# JTAG_Flash_Update.net
KiCad netlist of a schematic drawn in Altium Designer
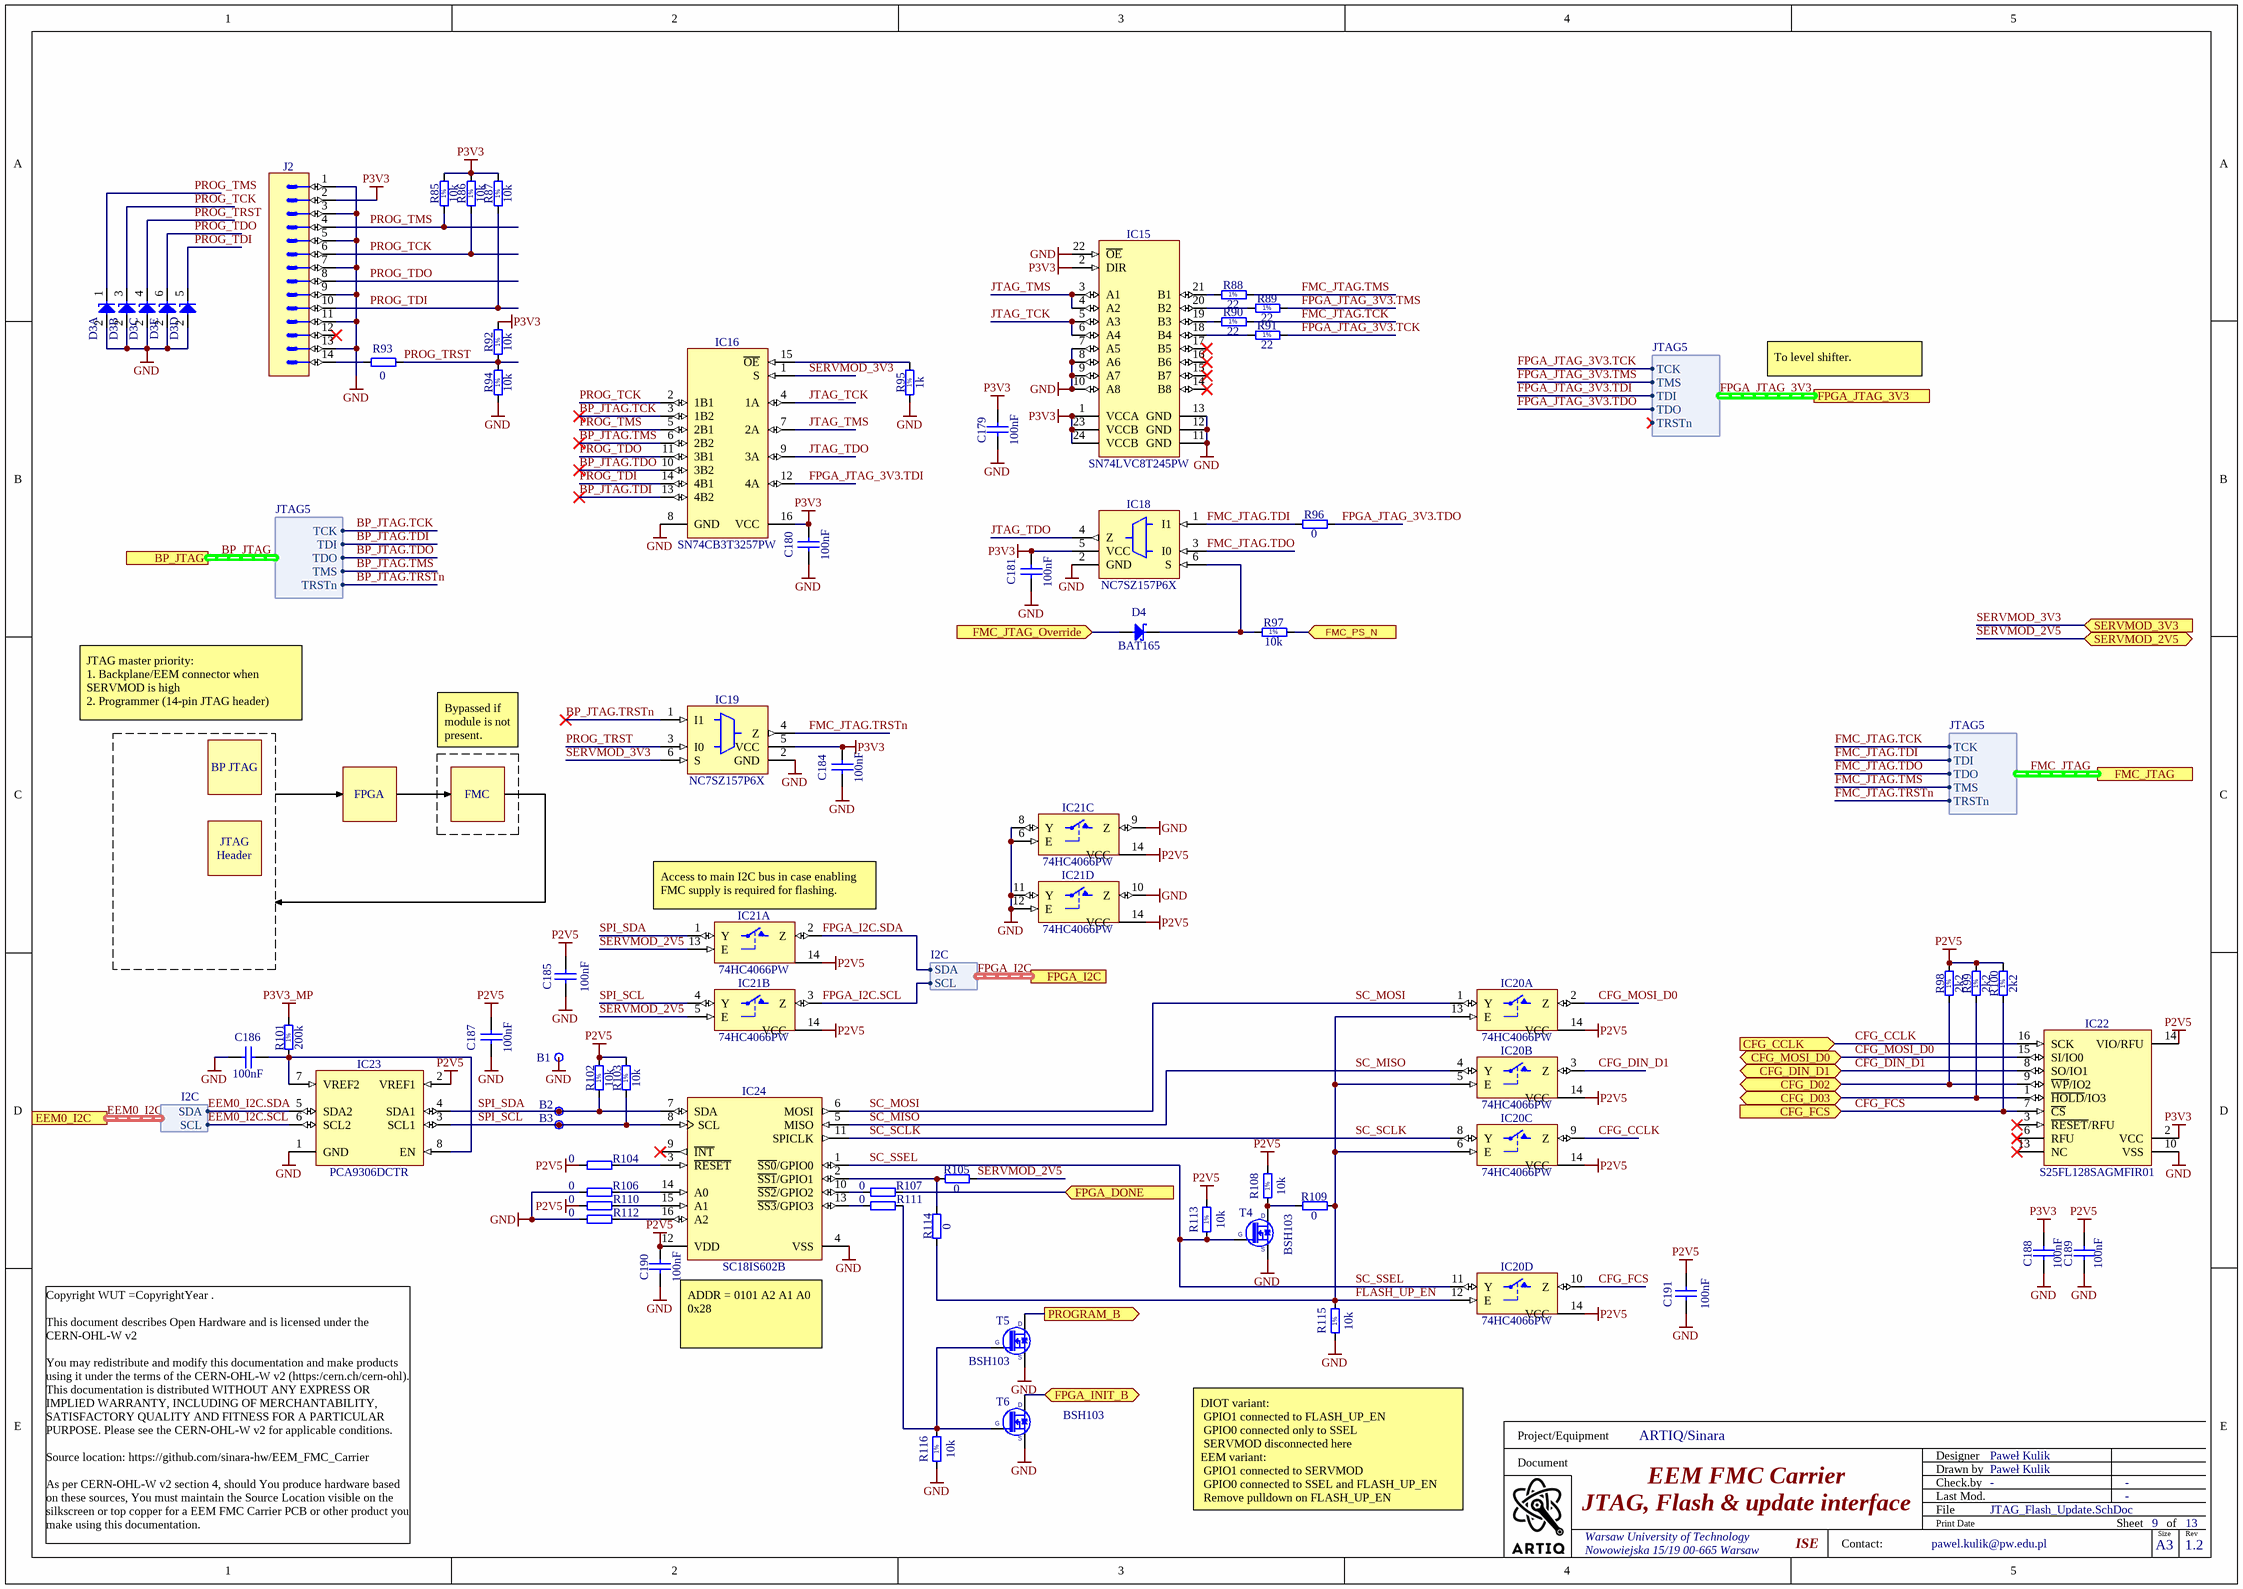
[diagram p0: JTAG_Flash_Update.SchDoc]

(export (version "E")
  (design (tool "Eeschema 10.0.6"))
  (components
    (comp (ref "B1")
      (value "Plated Hole")
      (footprint "c150h100")
      (description "Single Terminal Socket")
      (fields (field (name "PART NUMBER") "PLATED_HOLE1.0_PAD1.5") (field (name "AUTHOR") "CERN DEM JLC"))
      (libsource (lib "Eletro-mechanical") (part "Single Terminal Socket"))
    )
    (comp (ref "B2")
      (value "Test Point")
      (footprint "TPS127")
      (fields (field (name "PART NUMBER") "SMD_PAD_1.27X1.27MM") (field (name "AUTHOR") "CERN DEM JLC"))
      (libsource (lib "Eletro-mechanical") (part "Test Point"))
    )
    (comp (ref "B3")
      (value "Test Point")
      (footprint "TPS127")
      (fields (field (name "PART NUMBER") "SMD_PAD_1.27X1.27MM") (field (name "AUTHOR") "CERN DEM JLC"))
      (libsource (lib "Eletro-mechanical") (part "Test Point"))
    )
    (comp (ref "C179")
      (value "100nF")
      (footprint "CAPC1005X55N")
      (description "Non-polarised capacitor")
      (fields
        (field (name "PART NUMBER") "CC0402_100NF_25V_10%_X7R_YUDEN_TMK105B7104KVHF")
        (field (name "VOLTAGE") "25V")
        (field (name "AUTHOR") "CERN DEM JLC")
      )
      (libsource (lib "Capacitors") (part "Capacitor - non polarized"))
    )
    (comp (ref "C180")
      (value "100nF")
      (footprint "CAPC1005X55N")
      (description "Non-polarised capacitor")
      (fields
        (field (name "PART NUMBER") "CC0402_100NF_25V_10%_X7R_YUDEN_TMK105B7104KVHF")
        (field (name "VOLTAGE") "25V")
        (field (name "AUTHOR") "CERN DEM JLC")
      )
      (libsource (lib "Capacitors") (part "Capacitor - non polarized"))
    )
    (comp (ref "C181")
      (value "100nF")
      (footprint "CAPC1005X55N")
      (description "Non-polarised capacitor")
      (fields
        (field (name "PART NUMBER") "CC0402_100NF_25V_10%_X7R_YUDEN_TMK105B7104KVHF")
        (field (name "VOLTAGE") "25V")
        (field (name "AUTHOR") "CERN DEM JLC")
      )
      (libsource (lib "Capacitors") (part "Capacitor - non polarized"))
    )
    (comp (ref "C184")
      (value "100nF")
      (footprint "CAPC1005X55N")
      (description "Non-polarised capacitor")
      (fields
        (field (name "PART NUMBER") "CC0402_100NF_25V_10%_X7R_YUDEN_TMK105B7104KVHF")
        (field (name "VOLTAGE") "25V")
        (field (name "AUTHOR") "CERN DEM JLC")
      )
      (libsource (lib "Capacitors") (part "Capacitor - non polarized"))
    )
    (comp (ref "C185")
      (value "100nF")
      (footprint "CAPC1005X55N")
      (description "Non-polarised capacitor")
      (fields
        (field (name "PART NUMBER") "CC0402_100NF_16V_10%_X5R")
        (field (name "VOLTAGE") "16V")
        (field (name "AUTHOR") "CERN DEM JLC")
      )
      (libsource (lib "Capacitors") (part "Capacitor - non polarized"))
    )
    (comp (ref "C186")
      (value "100nF")
      (footprint "CAPC1005X55N")
      (description "Non-polarised capacitor")
      (fields
        (field (name "PART NUMBER") "CC0402_100NF_25V_10%_X7R_YUDEN_TMK105B7104KVHF")
        (field (name "VOLTAGE") "25V")
        (field (name "AUTHOR") "CERN DEM JLC")
      )
      (libsource (lib "Capacitors") (part "Capacitor - non polarized"))
    )
    (comp (ref "C187")
      (value "100nF")
      (footprint "CAPC1005X55N")
      (description "Non-polarised capacitor")
      (fields
        (field (name "PART NUMBER") "CC0402_100NF_25V_10%_X7R_YUDEN_TMK105B7104KVHF")
        (field (name "VOLTAGE") "25V")
        (field (name "AUTHOR") "CERN DEM JLC")
      )
      (libsource (lib "Capacitors") (part "Capacitor - non polarized"))
    )
    (comp (ref "C188")
      (value "100nF")
      (footprint "CAPC0603X33N")
      (description "Non-polarised capacitor")
      (fields
        (field (name "PART NUMBER") "CC0201_100NF_6.3V_10%_X5R")
        (field (name "VOLTAGE") "6.3V")
        (field (name "AUTHOR") "CERN DEM JLC")
      )
      (libsource (lib "Capacitors") (part "Capacitor - non polarized"))
    )
    (comp (ref "C189")
      (value "100nF")
      (footprint "CAPC0603X33N")
      (description "Non-polarised capacitor")
      (fields
        (field (name "PART NUMBER") "CC0201_100NF_6.3V_10%_X5R")
        (field (name "VOLTAGE") "6.3V")
        (field (name "AUTHOR") "CERN DEM JLC")
      )
      (libsource (lib "Capacitors") (part "Capacitor - non polarized"))
    )
    (comp (ref "C190")
      (value "100nF")
      (footprint "CAPC1005X55N")
      (description "Non-polarised capacitor")
      (fields
        (field (name "PART NUMBER") "CC0402_100NF_16V_10%_X5R")
        (field (name "VOLTAGE") "16V")
        (field (name "AUTHOR") "CERN DEM JLC")
      )
      (libsource (lib "Capacitors") (part "Capacitor - non polarized"))
    )
    (comp (ref "C191")
      (value "100nF")
      (footprint "CAPC1005X55N")
      (description "Non-polarised capacitor")
      (fields
        (field (name "PART NUMBER") "CC0402_100NF_16V_10%_X5R")
        (field (name "VOLTAGE") "16V")
        (field (name "AUTHOR") "CERN DEM JLC")
      )
      (libsource (lib "Capacitors") (part "Capacitor - non polarized"))
    )
    (comp (ref "D3")
      (value "PESD3V3L5UY")
      (footprint "SOT65P210X110-6N")
      (description "Fivefold ESD Protection Diode Arrays")
      (fields
        (field (name "VOLTAGE") "3.3V")
        (field (name "POWER") "200W")
        (field (name "AUTHOR") "CERN DEM WB")
      )
      (libsource (lib "ICs And Semiconductors") (part "PESD Array 5diodes 6pins Common anode2"))
    )
    (comp (ref "D4")
      (value "BAT165")
      (footprint "SOD2512X110N")
      (description "Schottky Diode")
      (fields
        (field (name "MANUFACTURER") "INFINEON")
        (field (name "VOLTAGE") "40V")
        (field (name "AUTHOR") "CERN DEM JLC")
      )
      (libsource (lib "ICs And Semiconductors") (part "Diode Schottky"))
    )
    (comp (ref "IC15")
      (value "SN74LVC8T245PW")
      (footprint "SOP65P640X120-24N")
      (description "8-Bit Dual-Supply Bus Transceiver With Configurable Voltage Translation and 3-State Outputs")
      (fields (field (name "MANUFACTURER") "TEXAS INSTRUMENTS") (field (name "AUTHOR") "CERN DEM JLC"))
      (libsource (lib "ICs And Semiconductors") (part "748T245"))
    )
    (comp (ref "IC16")
      (value "SN74CB3T3257PW")
      (footprint "SOP65P640X120-16N")
      (description "4-BIT 1-OF-2 FET Multiplexer/Demultiplexer 2.5V/3.3V Low-Voltage Bus Switch 5V Tolerant Shifter")
      (fields (field (name "MANUFACTURER") "TEXAS INSTRUMENTS") (field (name "AUTHOR") "CERN DEM JLC"))
      (libsource (lib "ICs And Semiconductors") (part "743257"))
    )
    (comp (ref "IC18")
      (value "NC7SZ157P6X")
      (footprint "SOT65P210X110-6N")
      (description "TinyLogic® UHS 2-Input Non-Inverting Multiplexer")
      (fields (field (name "MANUFACTURER") "FAIRCHILD SEMICONDUCTOR") (field (name "AUTHOR") "CERN DEM JLC"))
      (libsource (lib "") (part "NC7SZ157_1"))
    )
    (comp (ref "IC19")
      (value "NC7SZ157P6X")
      (footprint "SOT65P210X110-6N")
      (description "TinyLogic® UHS 2-Input Non-Inverting Multiplexer")
      (fields (field (name "MANUFACTURER") "FAIRCHILD SEMICONDUCTOR") (field (name "AUTHOR") "CERN DEM JLC"))
      (libsource (lib "ICs And Semiconductors") (part "NC7SZ157"))
    )
    (comp (ref "IC20")
      (value "74HC4066PW")
      (footprint "SOP65P640X110-14N")
      (fields (field (name "MANUFACTURER") "NXP SEMICONDUCTORS") (field (name "AUTHOR") "CERN DEM JLC"))
      (libsource (lib "ICs And Semiconductors") (part "4066"))
    )
    (comp (ref "IC21")
      (value "74HC4066PW")
      (footprint "SOP65P640X110-14N")
      (fields (field (name "MANUFACTURER") "NXP SEMICONDUCTORS") (field (name "AUTHOR") "CERN DEM JLC"))
      (libsource (lib "ICs And Semiconductors") (part "4066"))
    )
    (comp (ref "IC22")
      (value "S25FL128SAGMFIR01")
      (footprint "SOIC127P1030X265-16N")
      (fields (field (name "MANUFACTURER") "SPANSION") (field (name "AUTHOR") "CERN DEM JLC"))
      (libsource (lib "ICs And Semiconductors") (part "S25FL128SAGMFIR01"))
    )
    (comp (ref "IC23")
      (value "PCA9306DCTR")
      (footprint "SOP65P400X130-8N")
      (description "Dual Bidirectional I2C Bus And SMBus Voltage-Level Translator")
      (fields (field (name "MANUFACTURER") "TEXAS INSTRUMENTS") (field (name "AUTHOR") "CERN DEM JLC"))
      (libsource (lib "ICs And Semiconductors") (part "PCA9306D"))
    )
    (comp (ref "IC24")
      (value "SC18IS602B")
      (footprint "SOP65P640X110-16N")
      (description "I2C-bus to SPI bridge")
      (fields (field (name "MANUFACTURER") "NXP SEMICONDUCTORS") (field (name "AUTHOR") "CERN DEM MR"))
      (libsource (lib "ICs And Semiconductors") (part "SC18IS602B"))
    )
    (comp (ref "J2")
      (value "Milli-Grid™")
      (footprint "MOLEX_87832-1420")
      (description "Connector 14 Male")
      (fields
        (field (name "PART NUMBER") "MOLEX_87832-1420")
        (field (name "MANUFACTURER") "MOLEX")
        (field (name "AUTHOR") "CERN DEM JLC")
      )
      (libsource (lib "Connectors") (part "Connector 14 Male"))
    )
    (comp (ref "R85")
      (value "10k")
      (footprint "RESC1005X40N")
      (description "Resistor - 1%")
      (fields
        (field (name "PART NUMBER") "R0402_10K_1%_0.0625W_100PPM")
        (field (name "POWER") "0.0625W")
        (field (name "AUTHOR") "CERN DEM JLC")
      )
      (libsource (lib "Resistors") (part "Resistor - 1%"))
    )
    (comp (ref "R86")
      (value "10k")
      (footprint "RESC1005X40N")
      (description "Resistor - 1%")
      (fields
        (field (name "PART NUMBER") "R0402_10K_1%_0.0625W_100PPM")
        (field (name "POWER") "0.0625W")
        (field (name "AUTHOR") "CERN DEM JLC")
      )
      (libsource (lib "Resistors") (part "Resistor - 1%"))
    )
    (comp (ref "R87")
      (value "10k")
      (footprint "RESC1005X40N")
      (description "Resistor - 1%")
      (fields
        (field (name "PART NUMBER") "R0402_10K_1%_0.0625W_100PPM")
        (field (name "POWER") "0.0625W")
        (field (name "AUTHOR") "CERN DEM JLC")
      )
      (libsource (lib "Resistors") (part "Resistor - 1%"))
    )
    (comp (ref "R88")
      (value "22")
      (footprint "RESC1005X40N")
      (description "Resistor - 1%")
      (fields
        (field (name "PART NUMBER") "R0402_22R_1%_0.0625W_100PPM")
        (field (name "POWER") "0.0625W")
        (field (name "AUTHOR") "CERN DEM JLC")
      )
      (libsource (lib "Resistors") (part "Resistor - 1%"))
    )
    (comp (ref "R89")
      (value "22")
      (footprint "RESC1005X40N")
      (description "Resistor - 1%")
      (fields
        (field (name "PART NUMBER") "R0402_22R_1%_0.0625W_100PPM")
        (field (name "POWER") "0.0625W")
        (field (name "AUTHOR") "CERN DEM JLC")
      )
      (libsource (lib "Resistors") (part "Resistor - 1%"))
    )
    (comp (ref "R90")
      (value "22")
      (footprint "RESC1005X40N")
      (description "Resistor - 1%")
      (fields
        (field (name "PART NUMBER") "R0402_22R_1%_0.0625W_100PPM")
        (field (name "POWER") "0.0625W")
        (field (name "AUTHOR") "CERN DEM JLC")
      )
      (libsource (lib "Resistors") (part "Resistor - 1%"))
    )
    (comp (ref "R91")
      (value "22")
      (footprint "RESC1005X40N")
      (description "Resistor - 1%")
      (fields
        (field (name "PART NUMBER") "R0402_22R_1%_0.0625W_100PPM")
        (field (name "POWER") "0.0625W")
        (field (name "AUTHOR") "CERN DEM JLC")
      )
      (libsource (lib "Resistors") (part "Resistor - 1%"))
    )
    (comp (ref "R92")
      (value "10k")
      (footprint "RESC1005X40N")
      (description "Resistor - 1%")
      (fields
        (field (name "PART NUMBER") "R0402_10K_1%_0.0625W_100PPM")
        (field (name "POWER") "0.0625W")
        (field (name "AUTHOR") "CERN DEM JLC")
      )
      (libsource (lib "Resistors") (part "Resistor - 1%"))
    )
    (comp (ref "R93")
      (value "0")
      (footprint "RESC1005X40N")
      (description "Resistor")
      (fields
        (field (name "MANUFACTURER PART NUMBER") "R0402_0R_JUMPER")
        (field (name "MANUFACTURER") "GENERIC")
        (field (name "AUTHOR") "CERN DEM JLC")
      )
      (libsource (lib "Resistors") (part "Resistor"))
    )
    (comp (ref "R94")
      (value "10k")
      (footprint "RESC1005X40N")
      (description "Resistor - 1%")
      (fields
        (field (name "PART NUMBER") "R0402_10K_1%_0.0625W_100PPM")
        (field (name "POWER") "0.0625W")
        (field (name "AUTHOR") "CERN DEM JLC")
      )
      (libsource (lib "Resistors") (part "Resistor - 1%"))
    )
    (comp (ref "R95")
      (value "1k")
      (footprint "RESC1005X40N")
      (description "Resistor - 1%")
      (fields
        (field (name "PART NUMBER") "R0402_1K_1%_0.0625W_100PPM")
        (field (name "POWER") "0.0625W")
        (field (name "AUTHOR") "CERN DEM JLC")
      )
      (libsource (lib "Resistors") (part "Resistor - 1%"))
    )
    (comp (ref "R96")
      (value "0")
      (footprint "RESC1005X40N")
      (description "Resistor")
      (fields
        (field (name "MANUFACTURER PART NUMBER") "R0402_0R_JUMPER")
        (field (name "MANUFACTURER") "GENERIC")
        (field (name "AUTHOR") "CERN DEM JLC")
      )
      (libsource (lib "Resistors") (part "Resistor"))
    )
    (comp (ref "R97")
      (value "10k")
      (footprint "RESC1005X40N")
      (description "Resistor - 1%")
      (fields
        (field (name "MANUFACTURER PART NUMBER") "R0402_10K_1%_0.0625W_100PPM")
        (field (name "MANUFACTURER") "GENERIC")
        (field (name "AUTHOR") "CERN DEM JLC")
      )
      (libsource (lib "Resistors") (part "Resistor - 1%"))
    )
    (comp (ref "R98")
      (value "2k2")
      (footprint "RESC1005X40N")
      (description "Resistor - 1%")
      (fields
        (field (name "PART NUMBER") "R0402_2K2_1%_0.0625W_100PPM")
        (field (name "POWER") "0.0625W")
        (field (name "AUTHOR") "CERN DEM JLC")
      )
      (libsource (lib "Resistors") (part "Resistor - 1%"))
    )
    (comp (ref "R99")
      (value "2k2")
      (footprint "RESC1005X40N")
      (description "Resistor - 1%")
      (fields
        (field (name "PART NUMBER") "R0402_2K2_1%_0.0625W_100PPM")
        (field (name "POWER") "0.0625W")
        (field (name "AUTHOR") "CERN DEM JLC")
      )
      (libsource (lib "Resistors") (part "Resistor - 1%"))
    )
    (comp (ref "R100")
      (value "2k2")
      (footprint "RESC1005X40N")
      (description "Resistor - 1%")
      (fields
        (field (name "PART NUMBER") "R0402_2K2_1%_0.0625W_100PPM")
        (field (name "POWER") "0.0625W")
        (field (name "AUTHOR") "CERN DEM JLC")
      )
      (libsource (lib "Resistors") (part "Resistor - 1%"))
    )
    (comp (ref "R101")
      (value "200k")
      (footprint "RESC1005X40N")
      (description "Resistor - 1%")
      (fields
        (field (name "PART NUMBER") "R0402_200K_1%_0.0625W_100PPM")
        (field (name "POWER") "0.0625W")
        (field (name "AUTHOR") "CERN DEM JLC")
      )
      (libsource (lib "Resistors") (part "Resistor - 1%"))
    )
    (comp (ref "R102")
      (value "10k")
      (footprint "RESC1005X40N")
      (description "Resistor - 1%")
      (fields
        (field (name "PART NUMBER") "R0402_10K_1%_0.0625W_100PPM")
        (field (name "POWER") "0.0625W")
        (field (name "AUTHOR") "CERN DEM JLC")
      )
      (libsource (lib "Resistors") (part "Resistor - 1%"))
    )
    (comp (ref "R103")
      (value "10k")
      (footprint "RESC1005X40N")
      (description "Resistor - 1%")
      (fields
        (field (name "PART NUMBER") "R0402_10K_1%_0.0625W_100PPM")
        (field (name "POWER") "0.0625W")
        (field (name "AUTHOR") "CERN DEM JLC")
      )
      (libsource (lib "Resistors") (part "Resistor - 1%"))
    )
    (comp (ref "R104")
      (value "0")
      (footprint "RESC1005X40N")
      (description "Resistor")
      (fields
        (field (name "PART NUMBER") "R0402_0R_JUMPER")
        (field (name "MANUFACTURER") "GENERIC")
        (field (name "AUTHOR") "CERN DEM JLC")
      )
      (libsource (lib "Resistors") (part "Resistor"))
    )
    (comp (ref "R105")
      (value "0")
      (footprint "RESC1005X40N")
      (description "Resistor")
      (fields
        (field (name "PART NUMBER") "R0402_0R_JUMPER")
        (field (name "MANUFACTURER") "GENERIC")
        (field (name "AUTHOR") "CERN DEM JLC")
      )
      (libsource (lib "Resistors") (part "Resistor"))
    )
    (comp (ref "R106")
      (value "0")
      (footprint "RESC1005X40N")
      (description "Resistor")
      (fields
        (field (name "PART NUMBER") "R0402_0R_JUMPER")
        (field (name "MANUFACTURER") "GENERIC")
        (field (name "AUTHOR") "CERN DEM JLC")
      )
      (libsource (lib "Resistors") (part "Resistor"))
    )
    (comp (ref "R107")
      (value "0")
      (footprint "RESC1005X40N")
      (description "Resistor")
      (fields
        (field (name "PART NUMBER") "R0402_0R_JUMPER")
        (field (name "MANUFACTURER") "GENERIC")
        (field (name "AUTHOR") "CERN DEM JLC")
      )
      (libsource (lib "Resistors") (part "Resistor"))
    )
    (comp (ref "R108")
      (value "10k")
      (footprint "RESC1005X40N")
      (description "Resistor - 1%")
      (fields
        (field (name "PART NUMBER") "R0402_10K_1%_0.0625W_100PPM")
        (field (name "POWER") "0.0625W")
        (field (name "AUTHOR") "CERN DEM JLC")
      )
      (libsource (lib "Resistors") (part "Resistor - 1%"))
    )
    (comp (ref "R109")
      (value "0")
      (footprint "RESC1005X40N")
      (description "Resistor")
      (fields
        (field (name "PART NUMBER") "R0402_0R_JUMPER")
        (field (name "MANUFACTURER") "GENERIC")
        (field (name "AUTHOR") "CERN DEM JLC")
      )
      (libsource (lib "Resistors") (part "Resistor"))
    )
    (comp (ref "R110")
      (value "0")
      (footprint "RESC1005X40N")
      (description "Resistor")
      (fields
        (field (name "PART NUMBER") "R0402_0R_JUMPER")
        (field (name "MANUFACTURER") "GENERIC")
        (field (name "AUTHOR") "CERN DEM JLC")
      )
      (libsource (lib "Resistors") (part "Resistor"))
    )
    (comp (ref "R111")
      (value "0")
      (footprint "RESC1005X40N")
      (description "Resistor")
      (fields
        (field (name "PART NUMBER") "R0402_0R_JUMPER")
        (field (name "MANUFACTURER") "GENERIC")
        (field (name "AUTHOR") "CERN DEM JLC")
      )
      (libsource (lib "Resistors") (part "Resistor"))
    )
    (comp (ref "R112")
      (value "0")
      (footprint "RESC1005X40N")
      (description "Resistor")
      (fields
        (field (name "PART NUMBER") "R0402_0R_JUMPER")
        (field (name "MANUFACTURER") "GENERIC")
        (field (name "AUTHOR") "CERN DEM JLC")
      )
      (libsource (lib "Resistors") (part "Resistor"))
    )
    (comp (ref "R113")
      (value "10k")
      (footprint "RESC1005X40N")
      (description "Resistor - 1%")
      (fields
        (field (name "PART NUMBER") "R0402_10K_1%_0.0625W_100PPM")
        (field (name "POWER") "0.0625W")
        (field (name "AUTHOR") "CERN DEM JLC")
      )
      (libsource (lib "Resistors") (part "Resistor - 1%"))
    )
    (comp (ref "R114")
      (value "0")
      (footprint "RESC1005X40N")
      (description "Resistor")
      (fields
        (field (name "PART NUMBER") "R0402_0R_JUMPER")
        (field (name "MANUFACTURER") "GENERIC")
        (field (name "AUTHOR") "CERN DEM JLC")
      )
      (libsource (lib "Resistors") (part "Resistor"))
    )
    (comp (ref "R115")
      (value "10k")
      (footprint "RESC1005X40N")
      (description "Resistor - 1%")
      (fields
        (field (name "PART NUMBER") "R0402_10K_1%_0.0625W_100PPM")
        (field (name "POWER") "0.0625W")
        (field (name "AUTHOR") "CERN DEM JLC")
      )
      (libsource (lib "Resistors") (part "Resistor - 1%"))
    )
    (comp (ref "R116")
      (value "10k")
      (footprint "RESC1005X40N")
      (description "Resistor - 1%")
      (fields
        (field (name "PART NUMBER") "R0402_10K_1%_0.0625W_100PPM")
        (field (name "POWER") "0.0625W")
        (field (name "AUTHOR") "CERN DEM JLC")
      )
      (libsource (lib "Resistors") (part "Resistor - 1%"))
    )
    (comp (ref "T4")
      (value "BSH103")
      (footprint "SOT95P230X110-3N")
      (description "N-CHANNEL MOSFET WITH DIODE")
      (fields (field (name "MANUFACTURER") "NEXPERIA") (field (name "AUTHOR") "CERN DEM JLC"))
      (libsource (lib "ICs And Semiconductors") (part "N-MOSFET-D 1G 2S 3D"))
    )
    (comp (ref "T5")
      (value "BSH103")
      (footprint "SOT95P230X110-3N")
      (description "N-CHANNEL MOSFET WITH DIODE")
      (fields (field (name "MANUFACTURER") "NEXPERIA") (field (name "AUTHOR") "CERN DEM JLC"))
      (libsource (lib "ICs And Semiconductors") (part "N-MOSFET-D 1G 2S 3D"))
    )
    (comp (ref "T6")
      (value "BSH103")
      (footprint "SOT95P230X110-3N")
      (description "N-CHANNEL MOSFET WITH DIODE")
      (fields (field (name "MANUFACTURER") "NEXPERIA") (field (name "AUTHOR") "CERN DEM JLC"))
      (libsource (lib "ICs And Semiconductors") (part "N-MOSFET-D 1G 2S 3D"))
    )
  )
  (nets
    (net (code "6") (name "/BP_JTAG.TCK") (class "Default")
      (node (ref "IC16") (pin "3") (pinfunction "1B2_3") (pintype "bidirectional"))
    )
    (net (code "7") (name "/BP_JTAG.TDI") (class "Default")
      (node (ref "IC16") (pin "13") (pinfunction "4B2_13") (pintype "bidirectional"))
    )
    (net (code "8") (name "/BP_JTAG.TDO") (class "Default")
      (node (ref "IC16") (pin "10") (pinfunction "3B2_10") (pintype "bidirectional"))
    )
    (net (code "9") (name "/BP_JTAG.TMS") (class "Default")
      (node (ref "IC16") (pin "6") (pinfunction "2B2_6") (pintype "bidirectional"))
    )
    (net (code "10") (name "/BP_JTAG.TRSTn") (class "Default")
      (node (ref "IC19") (pin "1") (pinfunction "I1_1") (pintype "input"))
    )
    (net (code "12") (name "/CFG_CCLK") (class "Default")
      (node (ref "IC20") (pin "9") (pinfunction "Z_9") (pintype "bidirectional"))
      (node (ref "IC22") (pin "16") (pinfunction "SCK_16") (pintype "input"))
    )
    (net (code "13") (name "/CFG_D02") (class "Default")
      (node (ref "IC22") (pin "9") (pinfunction "~{WP}/IO2_9") (pintype "bidirectional"))
      (node (ref "R98") (pin "1") (pinfunction "1_1") (pintype "passive"))
    )
    (net (code "14") (name "/CFG_D03") (class "Default")
      (node (ref "IC22") (pin "1") (pinfunction "~{HOLD}/IO3_1") (pintype "bidirectional"))
      (node (ref "R99") (pin "1") (pinfunction "1_1") (pintype "passive"))
    )
    (net (code "15") (name "/CFG_DIN_D1") (class "Default")
      (node (ref "IC20") (pin "3") (pinfunction "Z_3") (pintype "bidirectional"))
      (node (ref "IC22") (pin "8") (pinfunction "SO/IO1_8") (pintype "bidirectional"))
    )
    (net (code "16") (name "/CFG_FCS") (class "Default")
      (node (ref "IC20") (pin "10") (pinfunction "Z_10") (pintype "bidirectional"))
      (node (ref "IC22") (pin "7") (pinfunction "~{CS}_7") (pintype "input"))
      (node (ref "R100") (pin "1") (pinfunction "1_1") (pintype "passive"))
    )
    (net (code "17") (name "/CFG_MOSI_D0") (class "Default")
      (node (ref "IC20") (pin "2") (pinfunction "Z_2") (pintype "bidirectional"))
      (node (ref "IC22") (pin "15") (pinfunction "SI/IO0_15") (pintype "bidirectional"))
    )
    (net (code "18") (name "/EEM0_I2C.SCL") (class "Default")
      (node (ref "IC23") (pin "6") (pinfunction "SCL2_6") (pintype "bidirectional"))
    )
    (net (code "19") (name "/EEM0_I2C.SDA") (class "Default")
      (node (ref "IC23") (pin "5") (pinfunction "SDA2_5") (pintype "bidirectional"))
    )
    (net (code "21") (name "/FLASH_UP_EN") (class "Default")
      (node (ref "IC20") (pin "12") (pinfunction "E_12") (pintype "input"))
      (node (ref "IC20") (pin "13") (pinfunction "E_13") (pintype "input"))
      (node (ref "IC20") (pin "5") (pinfunction "E_5") (pintype "input"))
      (node (ref "IC20") (pin "6") (pinfunction "E_6") (pintype "input"))
      (node (ref "R109") (pin "2") (pinfunction "2_2") (pintype "passive"))
      (node (ref "R114") (pin "1") (pinfunction "1_1") (pintype "passive"))
      (node (ref "R115") (pin "2") (pinfunction "2_2") (pintype "passive"))
    )
    (net (code "22") (name "/FMC_JTAG.TCK") (class "Default")
      (node (ref "R90") (pin "2") (pinfunction "2_2") (pintype "passive"))
    )
    (net (code "23") (name "/FMC_JTAG.TDI") (class "Default")
      (node (ref "IC18") (pin "1") (pinfunction "I1_1") (pintype "input"))
      (node (ref "R96") (pin "2") (pinfunction "2_2") (pintype "passive"))
    )
    (net (code "24") (name "/FMC_JTAG.TDO") (class "Default")
      (node (ref "IC18") (pin "3") (pinfunction "I0_3") (pintype "input"))
    )
    (net (code "25") (name "/FMC_JTAG.TMS") (class "Default")
      (node (ref "R88") (pin "2") (pinfunction "2_2") (pintype "passive"))
    )
    (net (code "26") (name "/FMC_JTAG.TRSTn") (class "Default")
      (node (ref "IC19") (pin "4") (pinfunction "Z_4") (pintype "output"))
    )
    (net (code "27") (name "/FMC_JTAG_Override") (class "Default")
      (node (ref "D4") (pin "2") (pinfunction "A_2") (pintype "passive"))
    )
    (net (code "29") (name "/FMC_PS_N") (class "Default")
      (node (ref "R97") (pin "2") (pinfunction "2_2") (pintype "passive"))
    )
    (net (code "30") (name "/FPGA_DONE") (class "Default")
      (node (ref "R107") (pin "1") (pinfunction "1_1") (pintype "passive"))
    )
    (net (code "31") (name "/FPGA_I2C.SCL") (class "Default")
      (node (ref "IC21") (pin "3") (pinfunction "Z_3") (pintype "bidirectional"))
    )
    (net (code "32") (name "/FPGA_I2C.SDA") (class "Default")
      (node (ref "IC21") (pin "2") (pinfunction "Z_2") (pintype "bidirectional"))
    )
    (net (code "34") (name "/FPGA_INIT_B") (class "Default")
      (node (ref "T6") (pin "3") (pinfunction "D_3") (pintype "passive"))
    )
    (net (code "35") (name "/FPGA_JTAG_3V3.TCK") (class "Default")
      (node (ref "R91") (pin "2") (pinfunction "2_2") (pintype "passive"))
    )
    (net (code "36") (name "/FPGA_JTAG_3V3.TDI") (class "Default")
      (node (ref "IC16") (pin "12") (pinfunction "4A_12") (pintype "bidirectional"))
    )
    (net (code "37") (name "/FPGA_JTAG_3V3.TDO") (class "Default")
      (node (ref "R96") (pin "1") (pinfunction "1_1") (pintype "passive"))
    )
    (net (code "38") (name "/FPGA_JTAG_3V3.TMS") (class "Default")
      (node (ref "R89") (pin "2") (pinfunction "2_2") (pintype "passive"))
    )
    (net (code "40") (name "/JTAG_TCK") (class "Default")
      (node (ref "IC15") (pin "5") (pinfunction "A3_5") (pintype "bidirectional"))
      (node (ref "IC15") (pin "6") (pinfunction "A4_6") (pintype "bidirectional"))
      (node (ref "IC16") (pin "4") (pinfunction "1A_4") (pintype "bidirectional"))
    )
    (net (code "41") (name "/JTAG_TDO") (class "Default")
      (node (ref "IC16") (pin "9") (pinfunction "3A_9") (pintype "bidirectional"))
      (node (ref "IC18") (pin "4") (pinfunction "Z_4") (pintype "output"))
    )
    (net (code "42") (name "/JTAG_TMS") (class "Default")
      (node (ref "IC15") (pin "3") (pinfunction "A1_3") (pintype "bidirectional"))
      (node (ref "IC15") (pin "4") (pinfunction "A2_4") (pintype "bidirectional"))
      (node (ref "IC16") (pin "7") (pinfunction "2A_7") (pintype "bidirectional"))
    )
    (net (code "43") (name "/PROGRAM_B") (class "Default")
      (node (ref "T5") (pin "3") (pinfunction "D_3") (pintype "passive"))
    )
    (net (code "44") (name "/PROG_TCK") (class "Default")
      (node (ref "D3") (pin "3") (pinfunction "C_3") (pintype "passive"))
      (node (ref "IC16") (pin "2") (pinfunction "1B1_2") (pintype "bidirectional"))
      (node (ref "J2") (pin "6") (pinfunction "6_6") (pintype "bidirectional"))
      (node (ref "R86") (pin "1") (pinfunction "1_1") (pintype "passive"))
    )
    (net (code "45") (name "/PROG_TDI") (class "Default")
      (node (ref "D3") (pin "5") (pinfunction "C_5") (pintype "passive"))
      (node (ref "IC16") (pin "14") (pinfunction "4B1_14") (pintype "bidirectional"))
      (node (ref "J2") (pin "10") (pinfunction "10_10") (pintype "bidirectional"))
      (node (ref "R87") (pin "1") (pinfunction "1_1") (pintype "passive"))
    )
    (net (code "46") (name "/PROG_TDO") (class "Default")
      (node (ref "D3") (pin "6") (pinfunction "C_6") (pintype "passive"))
      (node (ref "IC16") (pin "11") (pinfunction "3B1_11") (pintype "bidirectional"))
      (node (ref "J2") (pin "8") (pinfunction "8_8") (pintype "bidirectional"))
    )
    (net (code "47") (name "/PROG_TMS") (class "Default")
      (node (ref "D3") (pin "1") (pinfunction "C_1") (pintype "passive"))
      (node (ref "IC16") (pin "5") (pinfunction "2B1_5") (pintype "bidirectional"))
      (node (ref "J2") (pin "4") (pinfunction "4_4") (pintype "bidirectional"))
      (node (ref "R85") (pin "1") (pinfunction "1_1") (pintype "passive"))
    )
    (net (code "48") (name "/PROG_TRST") (class "Default")
      (node (ref "D3") (pin "4") (pinfunction "C_4") (pintype "passive"))
      (node (ref "IC19") (pin "3") (pinfunction "I0_3") (pintype "input"))
      (node (ref "R92") (pin "1") (pinfunction "1_1") (pintype "passive"))
      (node (ref "R93") (pin "1") (pinfunction "1_1") (pintype "passive"))
      (node (ref "R94") (pin "2") (pinfunction "2_2") (pintype "passive"))
    )
    (net (code "49") (name "/SC_MISO") (class "Default")
      (node (ref "IC20") (pin "4") (pinfunction "Y_4") (pintype "bidirectional"))
      (node (ref "IC24") (pin "5") (pinfunction "MISO_5") (pintype "input"))
    )
    (net (code "50") (name "/SC_MOSI") (class "Default")
      (node (ref "IC20") (pin "1") (pinfunction "Y_1") (pintype "bidirectional"))
      (node (ref "IC24") (pin "6") (pinfunction "MOSI_6") (pintype "output"))
    )
    (net (code "51") (name "/SC_SCLK") (class "Default")
      (node (ref "IC20") (pin "8") (pinfunction "Y_8") (pintype "bidirectional"))
      (node (ref "IC24") (pin "11") (pinfunction "SPICLK_11") (pintype "output"))
    )
    (net (code "52") (name "/SC_SSEL") (class "Default")
      (node (ref "IC20") (pin "11") (pinfunction "Y_11") (pintype "bidirectional"))
      (node (ref "IC24") (pin "1") (pinfunction "~{SS0}/GPIO0_1") (pintype "bidirectional"))
      (node (ref "R113") (pin "1") (pinfunction "1_1") (pintype "passive"))
      (node (ref "T4") (pin "1") (pinfunction "G_1") (pintype "passive"))
    )
    (net (code "53") (name "/SERVMOD_2V5") (class "Default")
      (node (ref "IC21") (pin "13") (pinfunction "E_13") (pintype "input"))
      (node (ref "IC21") (pin "5") (pinfunction "E_5") (pintype "input"))
      (node (ref "R105") (pin "2") (pinfunction "2_2") (pintype "passive"))
    )
    (net (code "54") (name "/SERVMOD_3V3") (class "Default")
      (node (ref "IC16") (pin "1") (pinfunction "S_1") (pintype "input"))
      (node (ref "IC19") (pin "6") (pinfunction "S_6") (pintype "input"))
    )
    (net (code "55") (name "/SPI_SCL") (class "Default")
      (node (ref "B3") (pin "1") (pinfunction "1_1") (pintype "bidirectional"))
      (node (ref "IC21") (pin "4") (pinfunction "Y_4") (pintype "bidirectional"))
      (node (ref "IC23") (pin "3") (pinfunction "SCL1_3") (pintype "bidirectional"))
      (node (ref "IC24") (pin "8") (pinfunction "SCL_8") (pintype "input"))
      (node (ref "R103") (pin "1") (pinfunction "1_1") (pintype "passive"))
    )
    (net (code "56") (name "/SPI_SDA") (class "Default")
      (node (ref "B2") (pin "1") (pinfunction "1_1") (pintype "bidirectional"))
      (node (ref "IC21") (pin "1") (pinfunction "Y_1") (pintype "bidirectional"))
      (node (ref "IC23") (pin "4") (pinfunction "SDA1_4") (pintype "bidirectional"))
      (node (ref "IC24") (pin "7") (pinfunction "SDA_7") (pintype "bidirectional"))
      (node (ref "R102") (pin "1") (pinfunction "1_1") (pintype "passive"))
    )
    (net (code "57") (name "GND") (class "Default")
      (node (ref "B1") (pin "1") (pinfunction "1_1") (pintype "bidirectional"))
      (node (ref "C179") (pin "1") (pinfunction "1_1") (pintype "passive"))
      (node (ref "C180") (pin "1") (pinfunction "1_1") (pintype "passive"))
      (node (ref "C181") (pin "1") (pinfunction "1_1") (pintype "passive"))
      (node (ref "C184") (pin "1") (pinfunction "1_1") (pintype "passive"))
      (node (ref "C185") (pin "1") (pinfunction "1_1") (pintype "passive"))
      (node (ref "C186") (pin "1") (pinfunction "1_1") (pintype "passive"))
      (node (ref "C187") (pin "1") (pinfunction "1_1") (pintype "passive"))
      (node (ref "C188") (pin "1") (pinfunction "1_1") (pintype "passive"))
      (node (ref "C189") (pin "1") (pinfunction "1_1") (pintype "passive"))
      (node (ref "C190") (pin "1") (pinfunction "1_1") (pintype "passive"))
      (node (ref "C191") (pin "1") (pinfunction "1_1") (pintype "passive"))
      (node (ref "D3") (pin "2") (pinfunction "A_2") (pintype "passive"))
      (node (ref "IC15") (pin "10") (pinfunction "A8_10") (pintype "bidirectional"))
      (node (ref "IC15") (pin "11") (pinfunction "GND_11") (pintype "power_in"))
      (node (ref "IC15") (pin "12") (pinfunction "GND_12") (pintype "power_in"))
      (node (ref "IC15") (pin "13") (pinfunction "GND_13") (pintype "power_in"))
      (node (ref "IC15") (pin "22") (pinfunction "~{OE}_22") (pintype "input"))
      (node (ref "IC15") (pin "7") (pinfunction "A5_7") (pintype "bidirectional"))
      (node (ref "IC15") (pin "8") (pinfunction "A6_8") (pintype "bidirectional"))
      (node (ref "IC15") (pin "9") (pinfunction "A7_9") (pintype "bidirectional"))
      (node (ref "IC16") (pin "8") (pinfunction "GND_8") (pintype "power_in"))
      (node (ref "IC18") (pin "2") (pinfunction "GND_2") (pintype "power_in"))
      (node (ref "IC19") (pin "2") (pinfunction "GND_2") (pintype "power_in"))
      (node (ref "IC20") (pin "7") (pinfunction "GND_7") (pintype "power_in"))
      (node (ref "IC21") (pin "10") (pinfunction "Z_10") (pintype "bidirectional"))
      (node (ref "IC21") (pin "11") (pinfunction "Y_11") (pintype "bidirectional"))
      (node (ref "IC21") (pin "12") (pinfunction "E_12") (pintype "input"))
      (node (ref "IC21") (pin "6") (pinfunction "E_6") (pintype "input"))
      (node (ref "IC21") (pin "7") (pinfunction "GND_7") (pintype "power_in"))
      (node (ref "IC21") (pin "8") (pinfunction "Y_8") (pintype "bidirectional"))
      (node (ref "IC21") (pin "9") (pinfunction "Z_9") (pintype "bidirectional"))
      (node (ref "IC22") (pin "10") (pinfunction "VSS_10") (pintype "power_in"))
      (node (ref "IC23") (pin "1") (pinfunction "GND_1") (pintype "power_in"))
      (node (ref "IC24") (pin "4") (pinfunction "VSS_4") (pintype "power_in"))
      (node (ref "J2") (pin "1") (pinfunction "1_1") (pintype "bidirectional"))
      (node (ref "J2") (pin "11") (pinfunction "11_11") (pintype "bidirectional"))
      (node (ref "J2") (pin "13") (pinfunction "13_13") (pintype "bidirectional"))
      (node (ref "J2") (pin "3") (pinfunction "3_3") (pintype "bidirectional"))
      (node (ref "J2") (pin "5") (pinfunction "5_5") (pintype "bidirectional"))
      (node (ref "J2") (pin "7") (pinfunction "7_7") (pintype "bidirectional"))
      (node (ref "J2") (pin "9") (pinfunction "9_9") (pintype "bidirectional"))
      (node (ref "R106") (pin "2") (pinfunction "2_2") (pintype "passive"))
      (node (ref "R112") (pin "2") (pinfunction "2_2") (pintype "passive"))
      (node (ref "R115") (pin "1") (pinfunction "1_1") (pintype "passive"))
      (node (ref "R116") (pin "1") (pinfunction "1_1") (pintype "passive"))
      (node (ref "R94") (pin "1") (pinfunction "1_1") (pintype "passive"))
      (node (ref "R95") (pin "1") (pinfunction "1_1") (pintype "passive"))
      (node (ref "T4") (pin "2") (pinfunction "S_2") (pintype "passive"))
      (node (ref "T5") (pin "2") (pinfunction "S_2") (pintype "passive"))
      (node (ref "T6") (pin "2") (pinfunction "S_2") (pintype "passive"))
    )
    (net (code "58") (name "Net-(D4-C)") (class "Default")
      (node (ref "D4") (pin "1") (pinfunction "C_1") (pintype "passive"))
      (node (ref "IC18") (pin "6") (pinfunction "S_6") (pintype "input"))
      (node (ref "R97") (pin "1") (pinfunction "1_1") (pintype "passive"))
    )
    (net (code "59") (name "Net-(IC15-B1)") (class "Default")
      (node (ref "IC15") (pin "21") (pinfunction "B1_21") (pintype "bidirectional"))
      (node (ref "R88") (pin "1") (pinfunction "1_1") (pintype "passive"))
    )
    (net (code "60") (name "Net-(IC15-B2)") (class "Default")
      (node (ref "IC15") (pin "20") (pinfunction "B2_20") (pintype "bidirectional"))
      (node (ref "R89") (pin "1") (pinfunction "1_1") (pintype "passive"))
    )
    (net (code "61") (name "Net-(IC15-B3)") (class "Default")
      (node (ref "IC15") (pin "19") (pinfunction "B3_19") (pintype "bidirectional"))
      (node (ref "R90") (pin "1") (pinfunction "1_1") (pintype "passive"))
    )
    (net (code "62") (name "Net-(IC15-B4)") (class "Default")
      (node (ref "IC15") (pin "18") (pinfunction "B4_18") (pintype "bidirectional"))
      (node (ref "R91") (pin "1") (pinfunction "1_1") (pintype "passive"))
    )
    (net (code "63") (name "Net-(IC16-~{OE})") (class "Default")
      (node (ref "IC16") (pin "15") (pinfunction "~{OE}_15") (pintype "input"))
      (node (ref "R95") (pin "2") (pinfunction "2_2") (pintype "passive"))
    )
    (net (code "64") (name "Net-(IC23-EN)") (class "Default")
      (node (ref "C186") (pin "2") (pinfunction "2_2") (pintype "passive"))
      (node (ref "IC23") (pin "7") (pinfunction "VREF2_7") (pintype "input"))
      (node (ref "IC23") (pin "8") (pinfunction "EN_8") (pintype "input"))
      (node (ref "R101") (pin "1") (pinfunction "1_1") (pintype "passive"))
    )
    (net (code "65") (name "Net-(IC24-A0)") (class "Default")
      (node (ref "IC24") (pin "14") (pinfunction "A0_14") (pintype "input"))
      (node (ref "R106") (pin "1") (pinfunction "1_1") (pintype "passive"))
    )
    (net (code "66") (name "Net-(IC24-A1)") (class "Default")
      (node (ref "IC24") (pin "15") (pinfunction "A1_15") (pintype "input"))
      (node (ref "R110") (pin "1") (pinfunction "1_1") (pintype "passive"))
    )
    (net (code "67") (name "Net-(IC24-A2)") (class "Default")
      (node (ref "IC24") (pin "16") (pinfunction "A2_16") (pintype "bidirectional"))
      (node (ref "R112") (pin "1") (pinfunction "1_1") (pintype "passive"))
    )
    (net (code "68") (name "Net-(IC24-~{RESET})") (class "Default")
      (node (ref "IC24") (pin "3") (pinfunction "~{RESET}_3") (pintype "input"))
      (node (ref "R104") (pin "1") (pinfunction "1_1") (pintype "passive"))
    )
    (net (code "69") (name "Net-(IC24-~{SS1}{slash}GPIO1)") (class "Default")
      (node (ref "IC24") (pin "2") (pinfunction "~{SS1}/GPIO1_2") (pintype "bidirectional"))
      (node (ref "R105") (pin "1") (pinfunction "1_1") (pintype "passive"))
      (node (ref "R114") (pin "2") (pinfunction "2_2") (pintype "passive"))
    )
    (net (code "70") (name "Net-(IC24-~{SS2}{slash}GPIO2)") (class "Default")
      (node (ref "IC24") (pin "10") (pinfunction "~{SS2}/GPIO2_10") (pintype "bidirectional"))
      (node (ref "R107") (pin "2") (pinfunction "2_2") (pintype "passive"))
    )
    (net (code "71") (name "Net-(IC24-~{SS3}{slash}GPIO3)") (class "Default")
      (node (ref "IC24") (pin "13") (pinfunction "~{SS3}/GPIO3_13") (pintype "bidirectional"))
      (node (ref "R111") (pin "2") (pinfunction "2_2") (pintype "passive"))
    )
    (net (code "72") (name "Net-(J2-Pad14)") (class "Default")
      (node (ref "J2") (pin "14") (pinfunction "14_14") (pintype "bidirectional"))
      (node (ref "R93") (pin "2") (pinfunction "2_2") (pintype "passive"))
    )
    (net (code "73") (name "Net-(T4-D)") (class "Default")
      (node (ref "R108") (pin "1") (pinfunction "1_1") (pintype "passive"))
      (node (ref "R109") (pin "1") (pinfunction "1_1") (pintype "passive"))
      (node (ref "T4") (pin "3") (pinfunction "D_3") (pintype "passive"))
    )
    (net (code "74") (name "Net-(T5-G)") (class "Default")
      (node (ref "R111") (pin "1") (pinfunction "1_1") (pintype "passive"))
      (node (ref "R116") (pin "2") (pinfunction "2_2") (pintype "passive"))
      (node (ref "T5") (pin "1") (pinfunction "G_1") (pintype "passive"))
      (node (ref "T6") (pin "1") (pinfunction "G_1") (pintype "passive"))
    )
    (net (code "75") (name "P2V5") (class "Default")
      (node (ref "C185") (pin "2") (pinfunction "2_2") (pintype "passive"))
      (node (ref "C187") (pin "2") (pinfunction "2_2") (pintype "passive"))
      (node (ref "C189") (pin "2") (pinfunction "2_2") (pintype "passive"))
      (node (ref "C190") (pin "2") (pinfunction "2_2") (pintype "passive"))
      (node (ref "C191") (pin "2") (pinfunction "2_2") (pintype "passive"))
      (node (ref "IC20") (pin "14") (pinfunction "VCC_14") (pintype "power_in"))
      (node (ref "IC21") (pin "14") (pinfunction "VCC_14") (pintype "power_in"))
      (node (ref "IC22") (pin "14") (pinfunction "VIO/RFU_14") (pintype "power_in"))
      (node (ref "IC23") (pin "2") (pinfunction "VREF1_2") (pintype "input"))
      (node (ref "IC24") (pin "12") (pinfunction "VDD_12") (pintype "power_in"))
      (node (ref "R100") (pin "2") (pinfunction "2_2") (pintype "passive"))
      (node (ref "R102") (pin "2") (pinfunction "2_2") (pintype "passive"))
      (node (ref "R103") (pin "2") (pinfunction "2_2") (pintype "passive"))
      (node (ref "R104") (pin "2") (pinfunction "2_2") (pintype "passive"))
      (node (ref "R108") (pin "2") (pinfunction "2_2") (pintype "passive"))
      (node (ref "R110") (pin "2") (pinfunction "2_2") (pintype "passive"))
      (node (ref "R113") (pin "2") (pinfunction "2_2") (pintype "passive"))
      (node (ref "R98") (pin "2") (pinfunction "2_2") (pintype "passive"))
      (node (ref "R99") (pin "2") (pinfunction "2_2") (pintype "passive"))
    )
    (net (code "76") (name "P3V3") (class "Default")
      (node (ref "C179") (pin "2") (pinfunction "2_2") (pintype "passive"))
      (node (ref "C180") (pin "2") (pinfunction "2_2") (pintype "passive"))
      (node (ref "C181") (pin "2") (pinfunction "2_2") (pintype "passive"))
      (node (ref "C184") (pin "2") (pinfunction "2_2") (pintype "passive"))
      (node (ref "C188") (pin "2") (pinfunction "2_2") (pintype "passive"))
      (node (ref "IC15") (pin "1") (pinfunction "VCCA_1") (pintype "power_in"))
      (node (ref "IC15") (pin "2") (pinfunction "DIR_2") (pintype "input"))
      (node (ref "IC15") (pin "23") (pinfunction "VCCB_23") (pintype "power_in"))
      (node (ref "IC15") (pin "24") (pinfunction "VCCB_24") (pintype "power_in"))
      (node (ref "IC16") (pin "16") (pinfunction "VCC_16") (pintype "power_in"))
      (node (ref "IC18") (pin "5") (pinfunction "VCC_5") (pintype "power_in"))
      (node (ref "IC19") (pin "5") (pinfunction "VCC_5") (pintype "power_in"))
      (node (ref "IC22") (pin "2") (pinfunction "VCC_2") (pintype "power_in"))
      (node (ref "J2") (pin "2") (pinfunction "2_2") (pintype "bidirectional"))
      (node (ref "R85") (pin "2") (pinfunction "2_2") (pintype "passive"))
      (node (ref "R86") (pin "2") (pinfunction "2_2") (pintype "passive"))
      (node (ref "R87") (pin "2") (pinfunction "2_2") (pintype "passive"))
      (node (ref "R92") (pin "2") (pinfunction "2_2") (pintype "passive"))
    )
    (net (code "77") (name "P3V3_MP") (class "Default")
      (node (ref "R101") (pin "2") (pinfunction "2_2") (pintype "passive"))
    )
    (net (code "78") (name "unconnected-(IC15-B5-Pad17)") (class "Default")
      (node (ref "IC15") (pin "17") (pinfunction "B5_17") (pintype "bidirectional+no_connect"))
    )
    (net (code "79") (name "unconnected-(IC15-B6-Pad16)") (class "Default")
      (node (ref "IC15") (pin "16") (pinfunction "B6_16") (pintype "bidirectional+no_connect"))
    )
    (net (code "80") (name "unconnected-(IC15-B7-Pad15)") (class "Default")
      (node (ref "IC15") (pin "15") (pinfunction "B7_15") (pintype "bidirectional+no_connect"))
    )
    (net (code "81") (name "unconnected-(IC15-B8-Pad14)") (class "Default")
      (node (ref "IC15") (pin "14") (pinfunction "B8_14") (pintype "bidirectional+no_connect"))
    )
    (net (code "82") (name "unconnected-(IC22-NC-Pad13)") (class "Default")
      (node (ref "IC22") (pin "13") (pinfunction "NC_13") (pintype "passive+no_connect"))
    )
    (net (code "83") (name "unconnected-(IC22-RFU-Pad6)") (class "Default")
      (node (ref "IC22") (pin "6") (pinfunction "RFU_6") (pintype "passive+no_connect"))
    )
    (net (code "84") (name "unconnected-(IC22-~{RESET}{slash}RFU-Pad3)") (class "Default")
      (node (ref "IC22") (pin "3") (pinfunction "~{RESET}/RFU_3") (pintype "input+no_connect"))
    )
    (net (code "85") (name "unconnected-(IC24-~{INT}-Pad9)") (class "Default")
      (node (ref "IC24") (pin "9") (pinfunction "~{INT}_9") (pintype "output+no_connect"))
    )
    (net (code "86") (name "unconnected-(J2-Pad12)") (class "Default")
      (node (ref "J2") (pin "12") (pinfunction "12_12") (pintype "bidirectional+no_connect"))
    )
  )
)
